# LED_Board.net
KiCad netlist of a schematic drawn in EAGLE
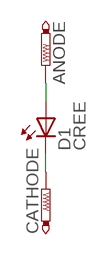
[diagram p0: schematic, sheet 1]

(export (version "E")
  (design (tool "Eeschema 10.0.6"))
  (components
    (comp (ref "ANODE")
      (value "PTR1PAD1-20")
      (footprint "eagle-import:P1-20")
      (libsource (lib "eagle-import") (part "PTR1PAD1-20"))
    )
    (comp (ref "CATHODE")
      (value "PTR1PAD1-20")
      (footprint "eagle-import:P1-20")
      (libsource (lib "eagle-import") (part "PTR1PAD1-20"))
    )
    (comp (ref "D1")
      (value "CREE")
      (footprint "eagle-import:CREE-XLAMP-XM-L")
      (libsource (lib "eagle-import") (part "CREE"))
    )
  )
  (nets
    (net (code "1") (name "Net-(ANODE-PadTP)") (class "Default")
      (node (ref "ANODE") (pin "TP") (pinfunction "TP_TP") (pintype "input"))
      (node (ref "D1") (pin "A") (pinfunction "A_A") (pintype "input"))
      (node (ref "D1") (pin "A@1") (pinfunction "A_A@1") (pintype "input"))
    )
    (net (code "2") (name "Net-(CATHODE-PadTP)") (class "Default")
      (node (ref "CATHODE") (pin "TP") (pinfunction "TP_TP") (pintype "input"))
      (node (ref "D1") (pin "C") (pinfunction "C_C") (pintype "output"))
      (node (ref "D1") (pin "C1") (pinfunction "C_C1") (pintype "output"))
      (node (ref "D1") (pin "C@1") (pinfunction "C_C@1") (pintype "output"))
    )
  )
)
